# MCU.net
KiCad netlist of a schematic drawn in Altium Designer
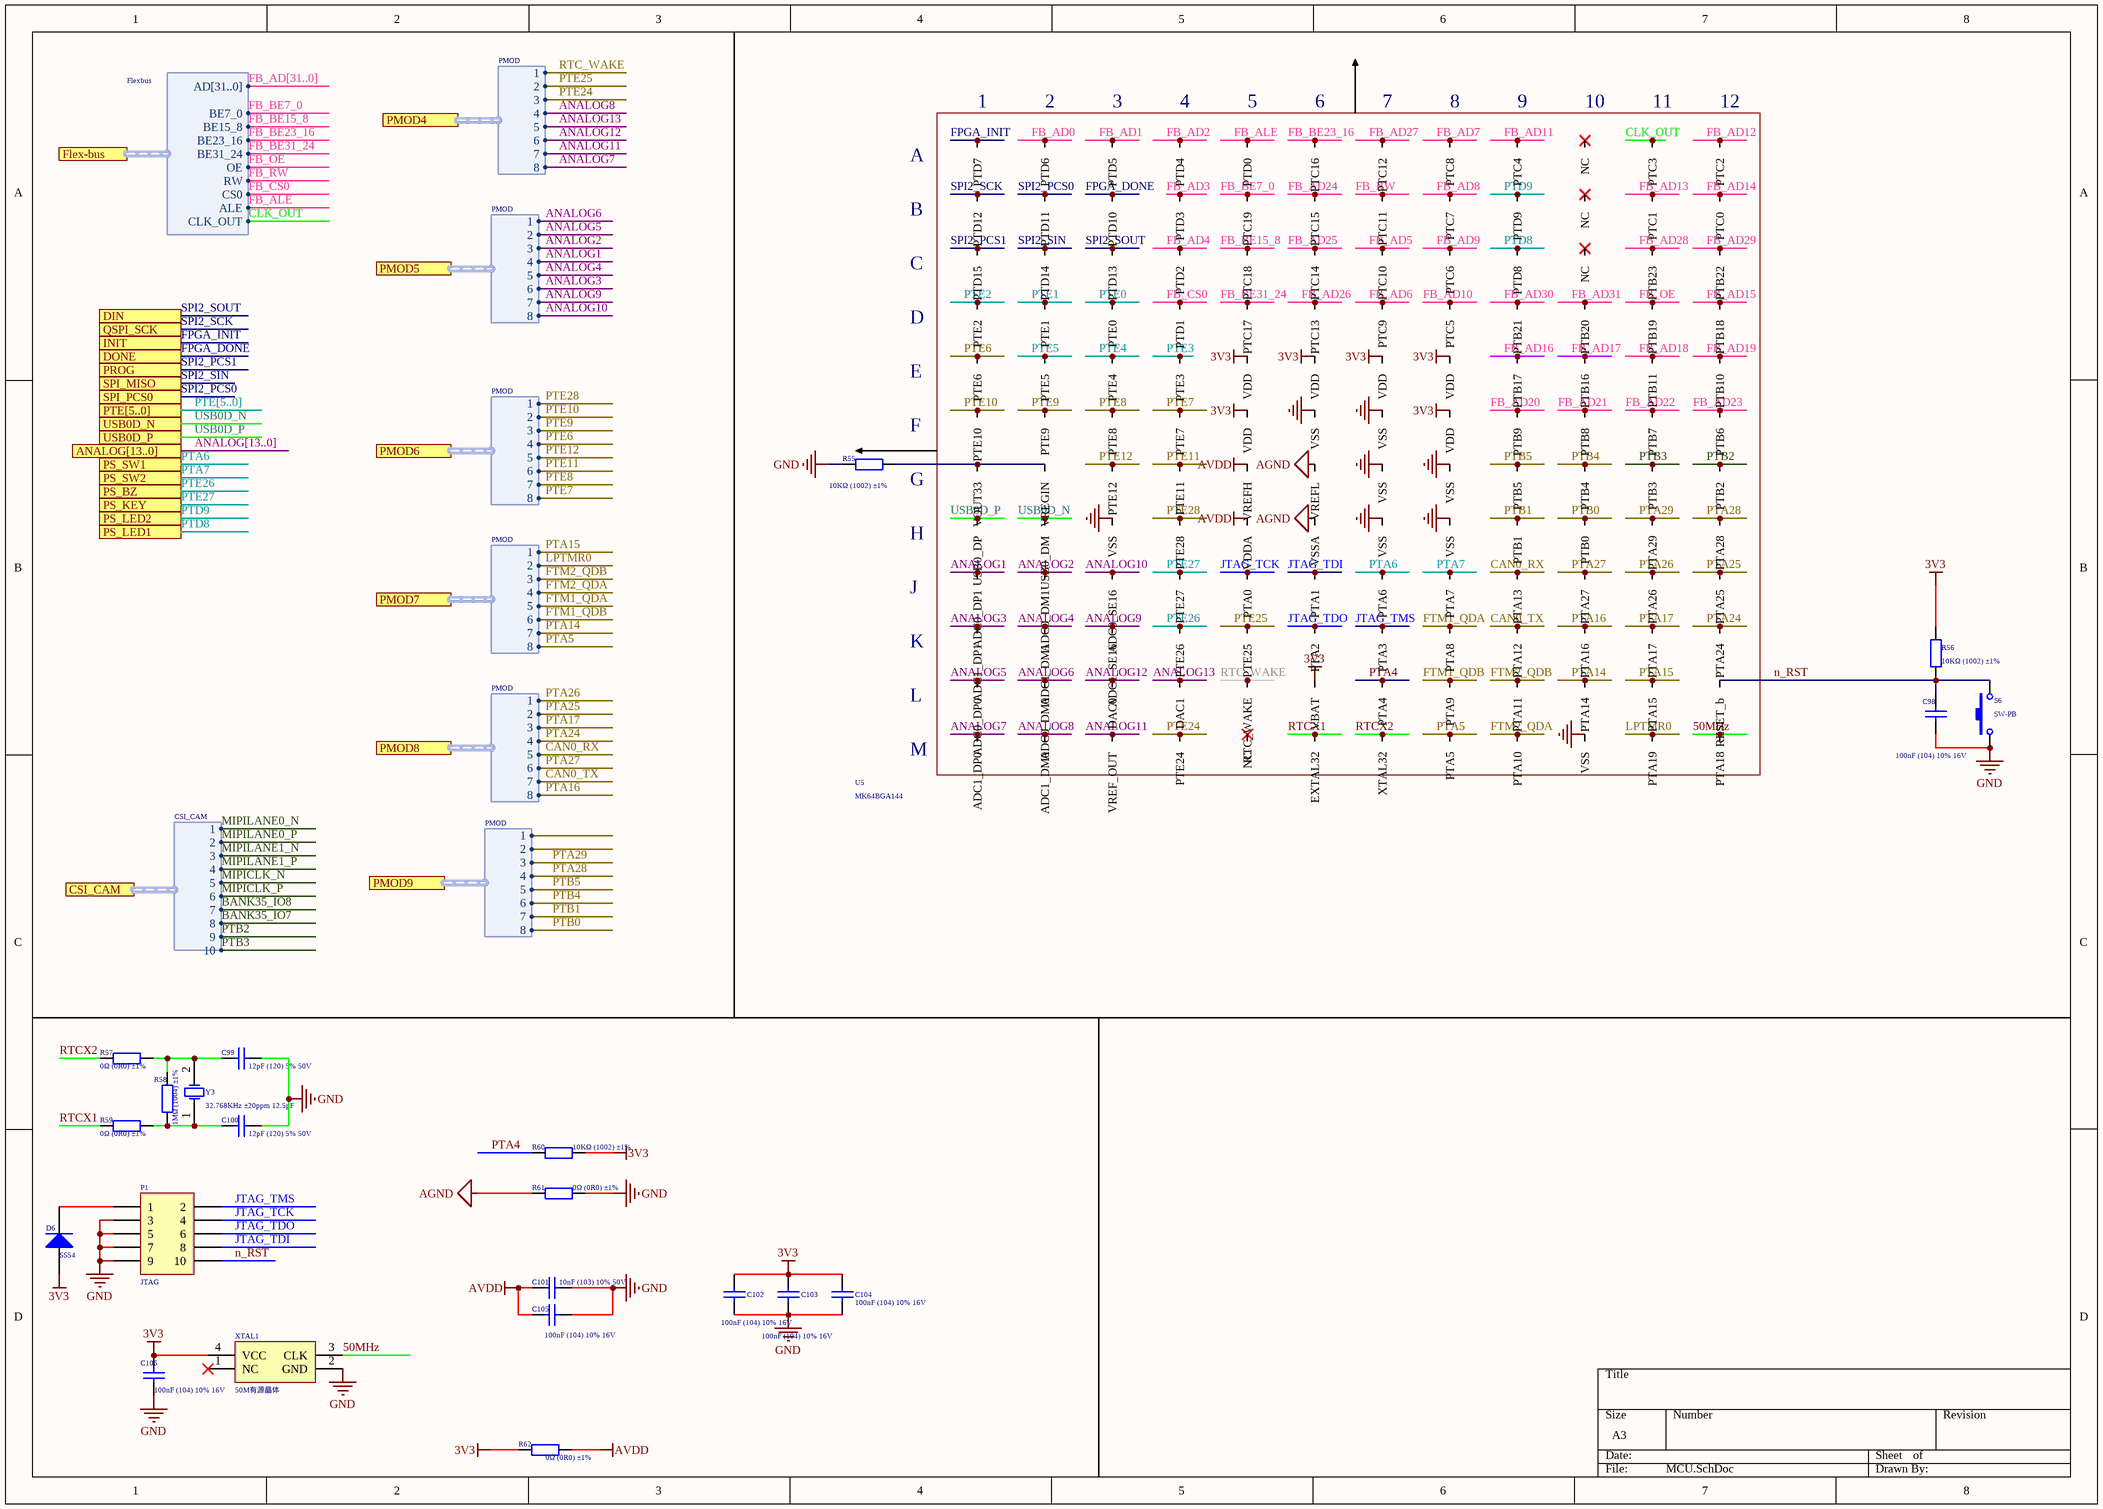
[diagram p0: MCU.SchDoc]

(export (version "E")
  (design (tool "Eeschema 10.0.6"))
  (components
    (comp (ref "C98")
      (value "100nF (104) 10% 16V")
      (footprint "0402_C")
      (description "贴片电容")
      (libsource (lib "Cap") (part "0402 100nF (104) 10% 16V"))
    )
    (comp (ref "C99")
      (value "12pF (120) 5% 50V")
      (footprint "0402_C")
      (description "贴片电容")
      (libsource (lib "Cap") (part "0402 12pF (120) 5% 50V"))
    )
    (comp (ref "C100")
      (value "12pF (120) 5% 50V")
      (footprint "0402_C")
      (description "贴片电容")
      (libsource (lib "Cap") (part "0402 12pF (120) 5% 50V"))
    )
    (comp (ref "C101")
      (value "10nF (103) 10% 50V")
      (footprint "0402_C")
      (description "贴片电容")
      (libsource (lib "Cap") (part "0402 10nF (103) 10% 50V"))
    )
    (comp (ref "C102")
      (value "100nF (104) 10% 16V")
      (footprint "0402_C")
      (description "贴片电容")
      (libsource (lib "Cap") (part "0402 100nF (104) 10% 16V"))
    )
    (comp (ref "C103")
      (value "100nF (104) 10% 16V")
      (footprint "0402_C")
      (description "贴片电容")
      (libsource (lib "Cap") (part "0402 100nF (104) 10% 16V"))
    )
    (comp (ref "C104")
      (value "100nF (104) 10% 16V")
      (footprint "0402_C")
      (description "贴片电容")
      (libsource (lib "Cap") (part "0402 100nF (104) 10% 16V"))
    )
    (comp (ref "C105")
      (value "100nF (104) 10% 16V")
      (footprint "0402_C")
      (description "贴片电容")
      (libsource (lib "Cap") (part "0402 100nF (104) 10% 16V"))
    )
    (comp (ref "C106")
      (value "100nF (104) 10% 16V")
      (footprint "0402_C")
      (description "贴片电容")
      (libsource (lib "Cap") (part "0402 100nF (104) 10% 16V"))
    )
    (comp (ref "D6")
      (value "SS54")
      (footprint "SMA(DO-214AC)_S1")
      (description "二极管")
      (libsource (lib "Miscellaneous Devices LC") (part "SMA(DO-214AC) SS54"))
    )
    (comp (ref "P1")
      (value "JTAG")
      (footprint "HDR2X5")
      (description "Header, 5-Pin, Dual row")
      (fields (field (name "PUBLISHER") "Altium Limited"))
      (libsource (lib "Sparks") (part "Header 5X2"))
    )
    (comp (ref "R55")
      (value "10KΩ (1002) ±1%")
      (footprint "0402_R")
      (description "贴片电阻")
      (libsource (lib "") (part "0402 10KΩ (1002) 1%_1"))
    )
    (comp (ref "R56")
      (value "10KΩ (1002) ±1%")
      (footprint "0402_R")
      (description "贴片电阻")
      (libsource (lib "RES") (part "0402 10KΩ (1002) 1%"))
    )
    (comp (ref "R57")
      (value "0Ω (0R0) ±1%")
      (footprint "0402_R")
      (description "贴片电阻")
      (libsource (lib "RES") (part "0402 0Ω (0R0) 1%"))
    )
    (comp (ref "R58")
      (value "1MΩ (1004) ±1%")
      (footprint "0402_R")
      (description "贴片电阻")
      (libsource (lib "RES") (part "0402 1MΩ (1004) 1%"))
    )
    (comp (ref "R59")
      (value "0Ω (0R0) ±1%")
      (footprint "0402_R")
      (description "贴片电阻")
      (libsource (lib "RES") (part "0402 0Ω (0R0) 1%"))
    )
    (comp (ref "R60")
      (value "10KΩ (1002) ±1%")
      (footprint "0402_R")
      (description "贴片电阻")
      (libsource (lib "") (part "0402 10KΩ (1002) 1%_1"))
    )
    (comp (ref "R61")
      (value "0Ω (0R0) ±1%")
      (footprint "0402_R")
      (description "贴片电阻")
      (libsource (lib "RES") (part "0402 0Ω (0R0) 1%"))
    )
    (comp (ref "R62")
      (value "0Ω (0R0) ±1%")
      (footprint "0402_R")
      (description "贴片电阻")
      (libsource (lib "Miscellaneous Devices LC") (part "0402 0Ω (0R0) 1%"))
    )
    (comp (ref "S6")
      (value "SW-PB")
      (footprint "key 3*4*2")
      (description "Switch")
      (libsource (lib "K60-V4.0") (part "SW-PB"))
    )
    (comp (ref "U5")
      (value "MK64BGA144")
      (footprint "BGA144C100P12X12_1300X1300X161")
      (libsource (lib "2号库") (part "MK64BGA144"))
    )
    (comp (ref "XTAL1") (value "50M有源晶体") (footprint "XTAL7_3225") (libsource (lib "Sparks") (part "有源晶体")))
    (comp (ref "Y3")
      (value "32.768KHz ±20ppm 12.5pF")
      (footprint "SMD-3215_2P FC - 135")
      (description "贴片晶振")
      (libsource (lib "CrystalOscillator") (part "SMD-3215_2P 32.768KHz 20ppm 12.5pF"))
    )
  )
  (nets
    (net (code "5") (name "/50MHz") (class "Default")
      (node (ref "U5") (pin "M12") (pinfunction "PTA18_M12") (pintype "passive"))
      (node (ref "XTAL1") (pin "3") (pinfunction "CLK_3") (pintype "passive"))
    )
    (net (code "6") (name "/ANALOG1") (class "Default")
      (node (ref "U5") (pin "J1") (pinfunction "ADC0_DP1_J1") (pintype "passive"))
    )
    (net (code "7") (name "/ANALOG2") (class "Default")
      (node (ref "U5") (pin "J2") (pinfunction "ADC0_DM1_J2") (pintype "passive"))
    )
    (net (code "8") (name "/ANALOG3") (class "Default")
      (node (ref "U5") (pin "K1") (pinfunction "ADC1_DP1_K1") (pintype "passive"))
    )
    (net (code "9") (name "/ANALOG4") (class "Default")
      (node (ref "U5") (pin "K2") (pinfunction "ADC1_DM1_K2") (pintype "passive"))
    )
    (net (code "10") (name "/ANALOG5") (class "Default")
      (node (ref "U5") (pin "L1") (pinfunction "ADC0_DP0_L1") (pintype "passive"))
    )
    (net (code "11") (name "/ANALOG6") (class "Default")
      (node (ref "U5") (pin "L2") (pinfunction "ADC0_DM0_L2") (pintype "passive"))
    )
    (net (code "12") (name "/ANALOG7") (class "Default")
      (node (ref "U5") (pin "M1") (pinfunction "ADC1_DP0_M1") (pintype "passive"))
    )
    (net (code "13") (name "/ANALOG8") (class "Default")
      (node (ref "U5") (pin "M2") (pinfunction "ADC1_DM0_M2") (pintype "passive"))
    )
    (net (code "14") (name "/ANALOG9") (class "Default")
      (node (ref "U5") (pin "K3") (pinfunction "ADC1_SE16_K3") (pintype "passive"))
    )
    (net (code "15") (name "/ANALOG10") (class "Default")
      (node (ref "U5") (pin "J3") (pinfunction "ADC0_SE16_J3") (pintype "passive"))
    )
    (net (code "16") (name "/ANALOG11") (class "Default")
      (node (ref "U5") (pin "M3") (pinfunction "VREF_OUT_M3") (pintype "passive"))
    )
    (net (code "17") (name "/ANALOG12") (class "Default")
      (node (ref "U5") (pin "L3") (pinfunction "DAC0_L3") (pintype "passive"))
    )
    (net (code "18") (name "/ANALOG13") (class "Default")
      (node (ref "U5") (pin "L4") (pinfunction "DAC1_L4") (pintype "passive"))
    )
    (net (code "22") (name "/CAN0_RX") (class "Default")
      (node (ref "U5") (pin "J9") (pinfunction "PTA13_J9") (pintype "passive"))
    )
    (net (code "23") (name "/CAN0_TX") (class "Default")
      (node (ref "U5") (pin "K9") (pinfunction "PTA12_K9") (pintype "passive"))
    )
    (net (code "24") (name "/CLK_OUT") (class "Default")
      (node (ref "U5") (pin "A11") (pinfunction "PTC3_A11") (pintype "passive"))
    )
    (net (code "25") (name "/FB_AD0") (class "Default")
      (node (ref "U5") (pin "A2") (pinfunction "PTD6_A2") (pintype "passive"))
    )
    (net (code "26") (name "/FB_AD1") (class "Default")
      (node (ref "U5") (pin "A3") (pinfunction "PTD5_A3") (pintype "passive"))
    )
    (net (code "27") (name "/FB_AD2") (class "Default")
      (node (ref "U5") (pin "A4") (pinfunction "PTD4_A4") (pintype "passive"))
    )
    (net (code "28") (name "/FB_AD3") (class "Default")
      (node (ref "U5") (pin "B4") (pinfunction "PTD3_B4") (pintype "passive"))
    )
    (net (code "29") (name "/FB_AD4") (class "Default")
      (node (ref "U5") (pin "C4") (pinfunction "PTD2_C4") (pintype "passive"))
    )
    (net (code "30") (name "/FB_AD5") (class "Default")
      (node (ref "U5") (pin "C7") (pinfunction "PTC10_C7") (pintype "passive"))
    )
    (net (code "31") (name "/FB_AD6") (class "Default")
      (node (ref "U5") (pin "D7") (pinfunction "PTC9_D7") (pintype "passive"))
    )
    (net (code "32") (name "/FB_AD7") (class "Default")
      (node (ref "U5") (pin "A8") (pinfunction "PTC8_A8") (pintype "passive"))
    )
    (net (code "33") (name "/FB_AD8") (class "Default")
      (node (ref "U5") (pin "B8") (pinfunction "PTC7_B8") (pintype "passive"))
    )
    (net (code "34") (name "/FB_AD9") (class "Default")
      (node (ref "U5") (pin "C8") (pinfunction "PTC6_C8") (pintype "passive"))
    )
    (net (code "35") (name "/FB_AD10") (class "Default")
      (node (ref "U5") (pin "D8") (pinfunction "PTC5_D8") (pintype "passive"))
    )
    (net (code "36") (name "/FB_AD11") (class "Default")
      (node (ref "U5") (pin "A9") (pinfunction "PTC4_A9") (pintype "passive"))
    )
    (net (code "37") (name "/FB_AD12") (class "Default")
      (node (ref "U5") (pin "A12") (pinfunction "PTC2_A12") (pintype "passive"))
    )
    (net (code "38") (name "/FB_AD13") (class "Default")
      (node (ref "U5") (pin "B11") (pinfunction "PTC1_B11") (pintype "passive"))
    )
    (net (code "39") (name "/FB_AD14") (class "Default")
      (node (ref "U5") (pin "B12") (pinfunction "PTC0_B12") (pintype "passive"))
    )
    (net (code "40") (name "/FB_AD15") (class "Default")
      (node (ref "U5") (pin "D12") (pinfunction "PTB18_D12") (pintype "passive"))
    )
    (net (code "41") (name "/FB_AD16") (class "Default")
      (node (ref "U5") (pin "E9") (pinfunction "PTB17_E9") (pintype "passive"))
    )
    (net (code "42") (name "/FB_AD17") (class "Default")
      (node (ref "U5") (pin "E10") (pinfunction "PTB16_E10") (pintype "passive"))
    )
    (net (code "43") (name "/FB_AD18") (class "Default")
      (node (ref "U5") (pin "E11") (pinfunction "PTB11_E11") (pintype "passive"))
    )
    (net (code "44") (name "/FB_AD19") (class "Default")
      (node (ref "U5") (pin "E12") (pinfunction "PTB10_E12") (pintype "passive"))
    )
    (net (code "45") (name "/FB_AD20") (class "Default")
      (node (ref "U5") (pin "F9") (pinfunction "PTB9_F9") (pintype "passive"))
    )
    (net (code "46") (name "/FB_AD21") (class "Default")
      (node (ref "U5") (pin "F10") (pinfunction "PTB8_F10") (pintype "passive"))
    )
    (net (code "47") (name "/FB_AD22") (class "Default")
      (node (ref "U5") (pin "F11") (pinfunction "PTB7_F11") (pintype "passive"))
    )
    (net (code "48") (name "/FB_AD23") (class "Default")
      (node (ref "U5") (pin "F12") (pinfunction "PTB6_F12") (pintype "passive"))
    )
    (net (code "49") (name "/FB_AD24") (class "Default")
      (node (ref "U5") (pin "B6") (pinfunction "PTC15_B6") (pintype "passive"))
    )
    (net (code "50") (name "/FB_AD25") (class "Default")
      (node (ref "U5") (pin "C6") (pinfunction "PTC14_C6") (pintype "passive"))
    )
    (net (code "51") (name "/FB_AD26") (class "Default")
      (node (ref "U5") (pin "D6") (pinfunction "PTC13_D6") (pintype "passive"))
    )
    (net (code "52") (name "/FB_AD27") (class "Default")
      (node (ref "U5") (pin "A7") (pinfunction "PTC12_A7") (pintype "passive"))
    )
    (net (code "53") (name "/FB_AD28") (class "Default")
      (node (ref "U5") (pin "C11") (pinfunction "PTB23_C11") (pintype "passive"))
    )
    (net (code "54") (name "/FB_AD29") (class "Default")
      (node (ref "U5") (pin "C12") (pinfunction "PTB22_C12") (pintype "passive"))
    )
    (net (code "55") (name "/FB_AD30") (class "Default")
      (node (ref "U5") (pin "D9") (pinfunction "PTB21_D9") (pintype "passive"))
    )
    (net (code "56") (name "/FB_AD31") (class "Default")
      (node (ref "U5") (pin "D10") (pinfunction "PTB20_D10") (pintype "passive"))
    )
    (net (code "57") (name "/FB_ALE") (class "Default")
      (node (ref "U5") (pin "A5") (pinfunction "PTD0_A5") (pintype "passive"))
    )
    (net (code "58") (name "/FB_BE7_0") (class "Default")
      (node (ref "U5") (pin "B5") (pinfunction "PTC19_B5") (pintype "passive"))
    )
    (net (code "59") (name "/FB_BE15_8") (class "Default")
      (node (ref "U5") (pin "C5") (pinfunction "PTC18_C5") (pintype "passive"))
    )
    (net (code "60") (name "/FB_BE23_16") (class "Default")
      (node (ref "U5") (pin "A6") (pinfunction "PTC16_A6") (pintype "passive"))
    )
    (net (code "61") (name "/FB_BE31_24") (class "Default")
      (node (ref "U5") (pin "D5") (pinfunction "PTC17_D5") (pintype "passive"))
    )
    (net (code "62") (name "/FB_CS0") (class "Default")
      (node (ref "U5") (pin "D4") (pinfunction "PTD1_D4") (pintype "passive"))
    )
    (net (code "63") (name "/FB_OE") (class "Default")
      (node (ref "U5") (pin "D11") (pinfunction "PTB19_D11") (pintype "passive"))
    )
    (net (code "64") (name "/FB_RW") (class "Default")
      (node (ref "U5") (pin "B7") (pinfunction "PTC11_B7") (pintype "passive"))
    )
    (net (code "65") (name "/FPGA_DONE") (class "Default")
      (node (ref "U5") (pin "B3") (pinfunction "PTD10_B3") (pintype "passive"))
    )
    (net (code "66") (name "/FPGA_INIT") (class "Default")
      (node (ref "U5") (pin "A1") (pinfunction "PTD7_A1") (pintype "passive"))
    )
    (net (code "67") (name "/FTM1_QDA") (class "Default")
      (node (ref "U5") (pin "K8") (pinfunction "PTA8_K8") (pintype "passive"))
    )
    (net (code "68") (name "/FTM1_QDB") (class "Default")
      (node (ref "U5") (pin "L8") (pinfunction "PTA9_L8") (pintype "passive"))
    )
    (net (code "69") (name "/FTM2_QDA") (class "Default")
      (node (ref "U5") (pin "M9") (pinfunction "PTA10_M9") (pintype "passive"))
    )
    (net (code "70") (name "/FTM2_QDB") (class "Default")
      (node (ref "U5") (pin "L9") (pinfunction "PTA11_L9") (pintype "passive"))
    )
    (net (code "72") (name "/JTAG_TCK") (class "Default")
      (node (ref "P1") (pin "4") (pinfunction "4_4") (pintype "passive"))
      (node (ref "U5") (pin "J5") (pinfunction "PTA0_J5") (pintype "passive"))
    )
    (net (code "73") (name "/JTAG_TDI") (class "Default")
      (node (ref "P1") (pin "8") (pinfunction "8_8") (pintype "passive"))
      (node (ref "U5") (pin "J6") (pinfunction "PTA1_J6") (pintype "passive"))
    )
    (net (code "74") (name "/JTAG_TDO") (class "Default")
      (node (ref "P1") (pin "6") (pinfunction "6_6") (pintype "passive"))
      (node (ref "U5") (pin "K6") (pinfunction "PTA2_K6") (pintype "passive"))
    )
    (net (code "75") (name "/JTAG_TMS") (class "Default")
      (node (ref "P1") (pin "2") (pinfunction "2_2") (pintype "passive"))
      (node (ref "U5") (pin "K7") (pinfunction "PTA3_K7") (pintype "passive"))
    )
    (net (code "76") (name "/LPTMR0") (class "Default")
      (node (ref "U5") (pin "M11") (pinfunction "PTA19_M11") (pintype "passive"))
    )
    (net (code "83") (name "/PTA4") (class "Default")
      (node (ref "R60") (pin "1") (pinfunction "1_1") (pintype "passive"))
      (node (ref "U5") (pin "L7") (pinfunction "PTA4_L7") (pintype "passive"))
    )
    (net (code "84") (name "/PTA5") (class "Default")
      (node (ref "U5") (pin "M8") (pinfunction "PTA5_M8") (pintype "passive"))
    )
    (net (code "85") (name "/PTA6") (class "Default")
      (node (ref "U5") (pin "J7") (pinfunction "PTA6_J7") (pintype "passive"))
    )
    (net (code "86") (name "/PTA7") (class "Default")
      (node (ref "U5") (pin "J8") (pinfunction "PTA7_J8") (pintype "passive"))
    )
    (net (code "87") (name "/PTA14") (class "Default")
      (node (ref "U5") (pin "L10") (pinfunction "PTA14_L10") (pintype "passive"))
    )
    (net (code "88") (name "/PTA15") (class "Default")
      (node (ref "U5") (pin "L11") (pinfunction "PTA15_L11") (pintype "passive"))
    )
    (net (code "89") (name "/PTA16") (class "Default")
      (node (ref "U5") (pin "K10") (pinfunction "PTA16_K10") (pintype "passive"))
    )
    (net (code "90") (name "/PTA17") (class "Default")
      (node (ref "U5") (pin "K11") (pinfunction "PTA17_K11") (pintype "passive"))
    )
    (net (code "91") (name "/PTA24") (class "Default")
      (node (ref "U5") (pin "K12") (pinfunction "PTA24_K12") (pintype "passive"))
    )
    (net (code "92") (name "/PTA25") (class "Default")
      (node (ref "U5") (pin "J12") (pinfunction "PTA25_J12") (pintype "passive"))
    )
    (net (code "93") (name "/PTA26") (class "Default")
      (node (ref "U5") (pin "J11") (pinfunction "PTA26_J11") (pintype "passive"))
    )
    (net (code "94") (name "/PTA27") (class "Default")
      (node (ref "U5") (pin "J10") (pinfunction "PTA27_J10") (pintype "passive"))
    )
    (net (code "95") (name "/PTA28") (class "Default")
      (node (ref "U5") (pin "H12") (pinfunction "PTA28_H12") (pintype "passive"))
    )
    (net (code "96") (name "/PTA29") (class "Default")
      (node (ref "U5") (pin "H11") (pinfunction "PTA29_H11") (pintype "passive"))
    )
    (net (code "97") (name "/PTB0") (class "Default")
      (node (ref "U5") (pin "H10") (pinfunction "PTB0_H10") (pintype "passive"))
    )
    (net (code "98") (name "/PTB1") (class "Default")
      (node (ref "U5") (pin "H9") (pinfunction "PTB1_H9") (pintype "passive"))
    )
    (net (code "99") (name "/PTB2") (class "Default")
      (node (ref "U5") (pin "G12") (pinfunction "PTB2_G12") (pintype "passive"))
    )
    (net (code "100") (name "/PTB3") (class "Default")
      (node (ref "U5") (pin "G11") (pinfunction "PTB3_G11") (pintype "passive"))
    )
    (net (code "101") (name "/PTB4") (class "Default")
      (node (ref "U5") (pin "G10") (pinfunction "PTB4_G10") (pintype "passive"))
    )
    (net (code "102") (name "/PTB5") (class "Default")
      (node (ref "U5") (pin "G9") (pinfunction "PTB5_G9") (pintype "passive"))
    )
    (net (code "103") (name "/PTD8") (class "Default")
      (node (ref "U5") (pin "C9") (pinfunction "PTD8_C9") (pintype "passive"))
    )
    (net (code "104") (name "/PTD9") (class "Default")
      (node (ref "U5") (pin "B9") (pinfunction "PTD9_B9") (pintype "passive"))
    )
    (net (code "105") (name "/PTE0") (class "Default")
      (node (ref "U5") (pin "D3") (pinfunction "PTE0_D3") (pintype "passive"))
    )
    (net (code "106") (name "/PTE1") (class "Default")
      (node (ref "U5") (pin "D2") (pinfunction "PTE1_D2") (pintype "passive"))
    )
    (net (code "107") (name "/PTE2") (class "Default")
      (node (ref "U5") (pin "D1") (pinfunction "PTE2_D1") (pintype "passive"))
    )
    (net (code "108") (name "/PTE3") (class "Default")
      (node (ref "U5") (pin "E4") (pinfunction "PTE3_E4") (pintype "passive"))
    )
    (net (code "109") (name "/PTE4") (class "Default")
      (node (ref "U5") (pin "E3") (pinfunction "PTE4_E3") (pintype "passive"))
    )
    (net (code "110") (name "/PTE5") (class "Default")
      (node (ref "U5") (pin "E2") (pinfunction "PTE5_E2") (pintype "passive"))
    )
    (net (code "111") (name "/PTE6") (class "Default")
      (node (ref "U5") (pin "E1") (pinfunction "PTE6_E1") (pintype "passive"))
    )
    (net (code "112") (name "/PTE7") (class "Default")
      (node (ref "U5") (pin "F4") (pinfunction "PTE7_F4") (pintype "passive"))
    )
    (net (code "113") (name "/PTE8") (class "Default")
      (node (ref "U5") (pin "F3") (pinfunction "PTE8_F3") (pintype "passive"))
    )
    (net (code "114") (name "/PTE9") (class "Default")
      (node (ref "U5") (pin "F2") (pinfunction "PTE9_F2") (pintype "passive"))
    )
    (net (code "115") (name "/PTE10") (class "Default")
      (node (ref "U5") (pin "F1") (pinfunction "PTE10_F1") (pintype "passive"))
    )
    (net (code "116") (name "/PTE11") (class "Default")
      (node (ref "U5") (pin "G4") (pinfunction "PTE11_G4") (pintype "passive"))
    )
    (net (code "117") (name "/PTE12") (class "Default")
      (node (ref "U5") (pin "G3") (pinfunction "PTE12_G3") (pintype "passive"))
    )
    (net (code "118") (name "/PTE24") (class "Default")
      (node (ref "U5") (pin "M4") (pinfunction "PTE24_M4") (pintype "passive"))
    )
    (net (code "119") (name "/PTE25") (class "Default")
      (node (ref "U5") (pin "K5") (pinfunction "PTE25_K5") (pintype "passive"))
    )
    (net (code "120") (name "/PTE26") (class "Default")
      (node (ref "U5") (pin "K4") (pinfunction "PTE26_K4") (pintype "passive"))
    )
    (net (code "121") (name "/PTE27") (class "Default")
      (node (ref "U5") (pin "J4") (pinfunction "PTE27_J4") (pintype "passive"))
    )
    (net (code "122") (name "/PTE28") (class "Default")
      (node (ref "U5") (pin "H4") (pinfunction "PTE28_H4") (pintype "passive"))
    )
    (net (code "124") (name "/RTCX1") (class "Default")
      (node (ref "R59") (pin "1") (pinfunction "1_1") (pintype "passive"))
      (node (ref "U5") (pin "M6") (pinfunction "EXTAL32_M6") (pintype "passive"))
    )
    (net (code "125") (name "/RTCX2") (class "Default")
      (node (ref "R57") (pin "1") (pinfunction "1_1") (pintype "passive"))
      (node (ref "U5") (pin "M7") (pinfunction "XTAL32_M7") (pintype "passive"))
    )
    (net (code "126") (name "/RTC_WAKE") (class "Default")
      (node (ref "U5") (pin "L5") (pinfunction "RTC_WAKE_L5") (pintype "passive"))
    )
    (net (code "127") (name "/SPI2_PCS0") (class "Default")
      (node (ref "U5") (pin "B2") (pinfunction "PTD11_B2") (pintype "passive"))
    )
    (net (code "128") (name "/SPI2_PCS1") (class "Default")
      (node (ref "U5") (pin "C1") (pinfunction "PTD15_C1") (pintype "passive"))
    )
    (net (code "129") (name "/SPI2_SCK") (class "Default")
      (node (ref "U5") (pin "B1") (pinfunction "PTD12_B1") (pintype "passive"))
    )
    (net (code "130") (name "/SPI2_SIN") (class "Default")
      (node (ref "U5") (pin "C2") (pinfunction "PTD14_C2") (pintype "passive"))
    )
    (net (code "131") (name "/SPI2_SOUT") (class "Default")
      (node (ref "U5") (pin "C3") (pinfunction "PTD13_C3") (pintype "passive"))
    )
    (net (code "132") (name "/USB0D_N") (class "Default")
      (node (ref "U5") (pin "H2") (pinfunction "USB0_DM_H2") (pintype "passive"))
    )
    (net (code "133") (name "/USB0D_P") (class "Default")
      (node (ref "U5") (pin "H1") (pinfunction "USB0_DP_H1") (pintype "passive"))
    )
    (net (code "134") (name "/n_RST") (class "Default")
      (node (ref "C98") (pin "2") (pinfunction "2_2") (pintype "passive"))
      (node (ref "P1") (pin "10") (pinfunction "10_10") (pintype "passive"))
      (node (ref "R56") (pin "1") (pinfunction "1_1") (pintype "passive"))
      (node (ref "S6") (pin "2") (pinfunction "2_2") (pintype "passive"))
      (node (ref "U5") (pin "L12") (pinfunction "RESET_b_L12") (pintype "passive"))
    )
    (net (code "138") (name "3V3") (class "Default")
      (node (ref "C102") (pin "2") (pinfunction "2_2") (pintype "passive"))
      (node (ref "C103") (pin "2") (pinfunction "2_2") (pintype "passive"))
      (node (ref "C104") (pin "2") (pinfunction "2_2") (pintype "passive"))
      (node (ref "C106") (pin "2") (pinfunction "2_2") (pintype "passive"))
      (node (ref "D6") (pin "1") (pinfunction "A_1") (pintype "passive"))
      (node (ref "R56") (pin "2") (pinfunction "2_2") (pintype "passive"))
      (node (ref "R60") (pin "2") (pinfunction "2_2") (pintype "passive"))
      (node (ref "R62") (pin "1") (pinfunction "1_1") (pintype "passive"))
      (node (ref "U5") (pin "E5") (pinfunction "VDD_E5") (pintype "passive"))
      (node (ref "U5") (pin "E6") (pinfunction "VDD_E6") (pintype "passive"))
      (node (ref "U5") (pin "E7") (pinfunction "VDD_E7") (pintype "passive"))
      (node (ref "U5") (pin "E8") (pinfunction "VDD_E8") (pintype "passive"))
      (node (ref "U5") (pin "F5") (pinfunction "VDD_F5") (pintype "passive"))
      (node (ref "U5") (pin "F8") (pinfunction "VDD_F8") (pintype "passive"))
      (node (ref "U5") (pin "L6") (pinfunction "VBAT_L6") (pintype "passive"))
      (node (ref "XTAL1") (pin "4") (pinfunction "VCC_4") (pintype "passive"))
    )
    (net (code "139") (name "AGND") (class "Default")
      (node (ref "R61") (pin "1") (pinfunction "1_1") (pintype "passive"))
      (node (ref "U5") (pin "G6") (pinfunction "VREFL_G6") (pintype "passive"))
      (node (ref "U5") (pin "H6") (pinfunction "VSSA_H6") (pintype "passive"))
    )
    (net (code "140") (name "AVDD") (class "Default")
      (node (ref "C101") (pin "1") (pinfunction "1_1") (pintype "passive"))
      (node (ref "C105") (pin "1") (pinfunction "1_1") (pintype "passive"))
      (node (ref "R62") (pin "2") (pinfunction "2_2") (pintype "passive"))
      (node (ref "U5") (pin "G5") (pinfunction "VREFH_G5") (pintype "passive"))
      (node (ref "U5") (pin "H5") (pinfunction "VDDA_H5") (pintype "passive"))
    )
    (net (code "141") (name "GND") (class "Default")
      (node (ref "C100") (pin "2") (pinfunction "2_2") (pintype "passive"))
      (node (ref "C101") (pin "2") (pinfunction "2_2") (pintype "passive"))
      (node (ref "C102") (pin "1") (pinfunction "1_1") (pintype "passive"))
      (node (ref "C103") (pin "1") (pinfunction "1_1") (pintype "passive"))
      (node (ref "C104") (pin "1") (pinfunction "1_1") (pintype "passive"))
      (node (ref "C105") (pin "2") (pinfunction "2_2") (pintype "passive"))
      (node (ref "C106") (pin "1") (pinfunction "1_1") (pintype "passive"))
      (node (ref "C98") (pin "1") (pinfunction "1_1") (pintype "passive"))
      (node (ref "C99") (pin "2") (pinfunction "2_2") (pintype "passive"))
      (node (ref "P1") (pin "3") (pinfunction "3_3") (pintype "passive"))
      (node (ref "P1") (pin "5") (pinfunction "5_5") (pintype "passive"))
      (node (ref "P1") (pin "7") (pinfunction "7_7") (pintype "passive"))
      (node (ref "P1") (pin "9") (pinfunction "9_9") (pintype "passive"))
      (node (ref "R55") (pin "1") (pinfunction "1_1") (pintype "passive"))
      (node (ref "R61") (pin "2") (pinfunction "2_2") (pintype "passive"))
      (node (ref "S6") (pin "1") (pinfunction "1_1") (pintype "passive"))
      (node (ref "U5") (pin "F6") (pinfunction "VSS_F6") (pintype "passive"))
      (node (ref "U5") (pin "F7") (pinfunction "VSS_F7") (pintype "passive"))
      (node (ref "U5") (pin "G7") (pinfunction "VSS_G7") (pintype "passive"))
      (node (ref "U5") (pin "G8") (pinfunction "VSS_G8") (pintype "passive"))
      (node (ref "U5") (pin "H3") (pinfunction "VSS_H3") (pintype "passive"))
      (node (ref "U5") (pin "H7") (pinfunction "VSS_H7") (pintype "passive"))
      (node (ref "U5") (pin "H8") (pinfunction "VSS_H8") (pintype "passive"))
      (node (ref "U5") (pin "M10") (pinfunction "VSS_M10") (pintype "passive"))
      (node (ref "XTAL1") (pin "2") (pinfunction "GND_2") (pintype "passive"))
    )
    (net (code "142") (name "Net-(D6-K)") (class "Default")
      (node (ref "D6") (pin "2") (pinfunction "K_2") (pintype "passive"))
      (node (ref "P1") (pin "1") (pinfunction "1_1") (pintype "passive"))
    )
    (net (code "143") (name "Net-(U5-VOUT33)") (class "Default")
      (node (ref "R55") (pin "2") (pinfunction "2_2") (pintype "passive"))
      (node (ref "U5") (pin "G1") (pinfunction "VOUT33_G1") (pintype "passive"))
      (node (ref "U5") (pin "G2") (pinfunction "VREGIN_G2") (pintype "passive"))
    )
    (net (code "144") (name "Net-(Y3-OSC1)") (class "Default")
      (node (ref "C100") (pin "1") (pinfunction "1_1") (pintype "passive"))
      (node (ref "R58") (pin "1") (pinfunction "1_1") (pintype "passive"))
      (node (ref "R59") (pin "2") (pinfunction "2_2") (pintype "passive"))
      (node (ref "Y3") (pin "1") (pinfunction "OSC1_1") (pintype "passive"))
    )
    (net (code "145") (name "Net-(Y3-OSC2)") (class "Default")
      (node (ref "C99") (pin "1") (pinfunction "1_1") (pintype "passive"))
      (node (ref "R57") (pin "2") (pinfunction "2_2") (pintype "passive"))
      (node (ref "R58") (pin "2") (pinfunction "2_2") (pintype "passive"))
      (node (ref "Y3") (pin "2") (pinfunction "OSC2_2") (pintype "passive"))
    )
    (net (code "146") (name "unconnected-(U5-NC-PadA10)") (class "Default")
      (node (ref "U5") (pin "A10") (pinfunction "NC_A10") (pintype "passive+no_connect"))
    )
    (net (code "147") (name "unconnected-(U5-NC-PadB10)") (class "Default")
      (node (ref "U5") (pin "B10") (pinfunction "NC_B10") (pintype "passive+no_connect"))
    )
    (net (code "148") (name "unconnected-(U5-NC-PadC10)") (class "Default")
      (node (ref "U5") (pin "C10") (pinfunction "NC_C10") (pintype "passive+no_connect"))
    )
    (net (code "149") (name "unconnected-(U5-NC-PadM5)") (class "Default")
      (node (ref "U5") (pin "M5") (pinfunction "NC_M5") (pintype "passive+no_connect"))
    )
    (net (code "150") (name "unconnected-(XTAL1-NC-Pad1)") (class "Default")
      (node (ref "XTAL1") (pin "1") (pinfunction "NC_1") (pintype "passive+no_connect"))
    )
  )
)
